# floorctrl.net
KiCad netlist of a schematic drawn in Altium Designer
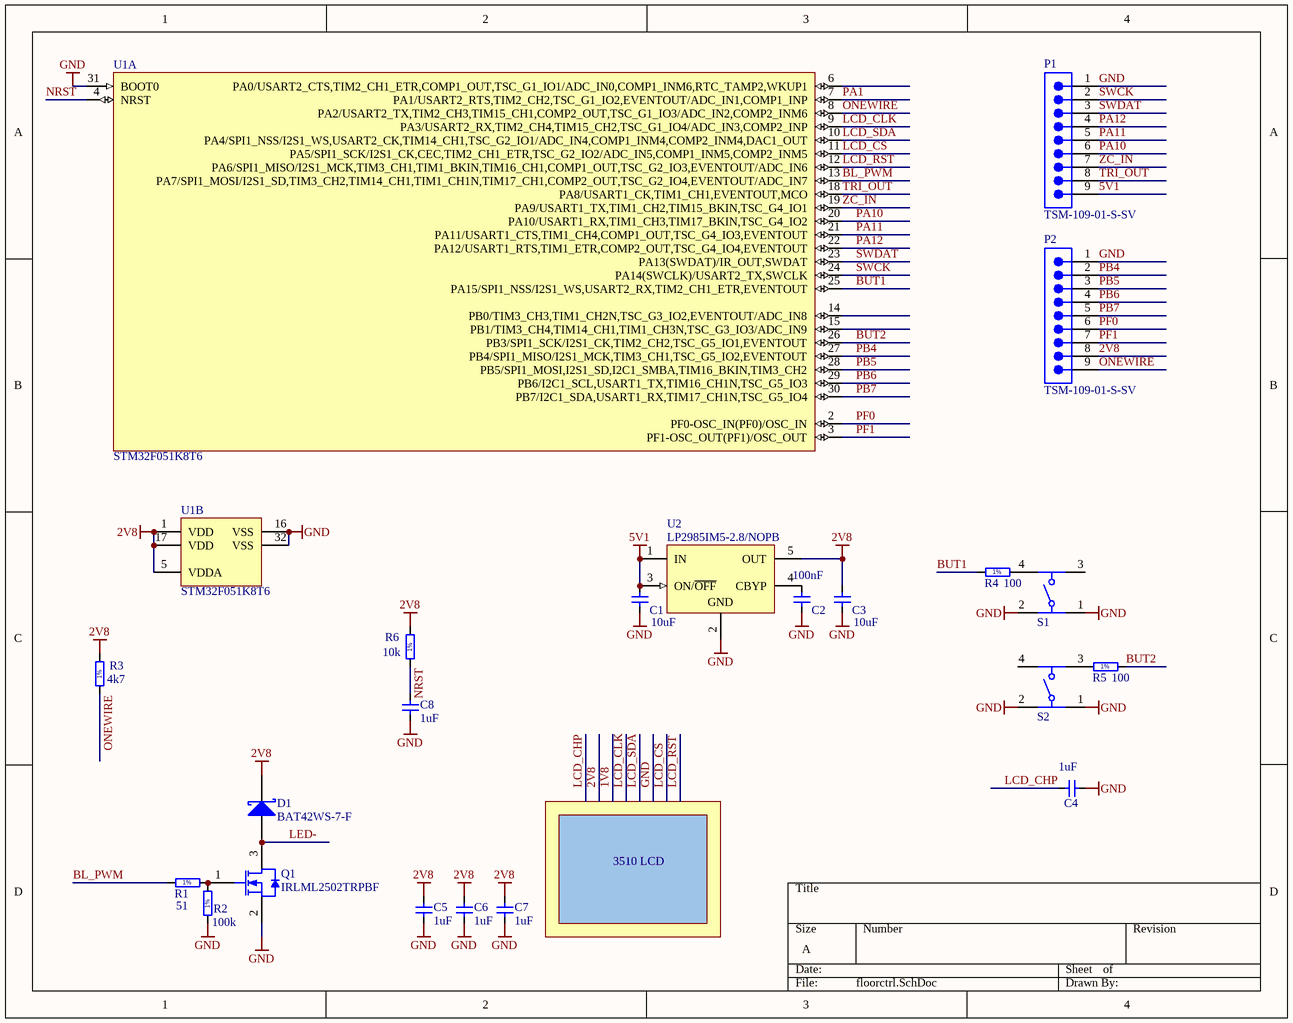
[diagram p0: floorctrl.SchDoc]

(export (version "E")
  (design (tool "Eeschema 10.0.6"))
  (components
    (comp (ref "C1")
      (value "10uF")
      (footprint "CAP0805R")
      (fields
        (field (name "PART NUMBER") "CC0805_10UF_16V_10%_X5R")
        (field (name "VOLTAGE") "16V")
        (field (name "TOLERANCE") "±10%")
        (field (name "AUTHOR") "I. Kuznetsov")
      )
      (libsource (lib "Capacitor") (part "CAP_NON_POLAR"))
    )
    (comp (ref "C2")
      (value "100nF")
      (footprint "CAP0805R")
      (fields
        (field (name "PART NUMBER") "CC0805_100NF_50V_10%_X7R")
        (field (name "VOLTAGE") "50V")
        (field (name "TOLERANCE") "±10%")
        (field (name "AUTHOR") "I. Kuznetsov")
      )
      (libsource (lib "Capacitor") (part "CAP_NON_POLAR"))
    )
    (comp (ref "C3")
      (value "10uF")
      (footprint "CAP0805R")
      (fields
        (field (name "PART NUMBER") "CC0805_10UF_16V_10%_X5R")
        (field (name "VOLTAGE") "16V")
        (field (name "TOLERANCE") "±10%")
        (field (name "AUTHOR") "I. Kuznetsov")
      )
      (libsource (lib "Capacitor") (part "CAP_NON_POLAR"))
    )
    (comp (ref "C4")
      (value "1uF")
      (footprint "CAP0805R")
      (fields
        (field (name "PART NUMBER") "CC0805_1UF_16V_10%_X7R")
        (field (name "VOLTAGE") "16V")
        (field (name "TOLERANCE") "±10%")
        (field (name "AUTHOR") "I. Kuznetsov")
      )
      (libsource (lib "Capacitor") (part "CAP_NON_POLAR"))
    )
    (comp (ref "C5")
      (value "1uF")
      (footprint "CAP0805R")
      (fields
        (field (name "PART NUMBER") "CC0805_1UF_16V_10%_X7R")
        (field (name "VOLTAGE") "16V")
        (field (name "TOLERANCE") "±10%")
        (field (name "AUTHOR") "I. Kuznetsov")
      )
      (libsource (lib "Capacitor") (part "CAP_NON_POLAR"))
    )
    (comp (ref "C6")
      (value "1uF")
      (footprint "CAP0805R")
      (fields
        (field (name "PART NUMBER") "CC0805_1UF_16V_10%_X7R")
        (field (name "VOLTAGE") "16V")
        (field (name "TOLERANCE") "±10%")
        (field (name "AUTHOR") "I. Kuznetsov")
      )
      (libsource (lib "Capacitor") (part "CAP_NON_POLAR"))
    )
    (comp (ref "C7")
      (value "1uF")
      (footprint "CAP0805R")
      (fields
        (field (name "PART NUMBER") "CC0805_1UF_16V_10%_X7R")
        (field (name "VOLTAGE") "16V")
        (field (name "TOLERANCE") "±10%")
        (field (name "AUTHOR") "I. Kuznetsov")
      )
      (libsource (lib "Capacitor") (part "CAP_NON_POLAR"))
    )
    (comp (ref "C8")
      (value "1uF")
      (footprint "CAP0805R")
      (fields
        (field (name "PART NUMBER") "CC0805_1UF_16V_10%_X7R")
        (field (name "VOLTAGE") "16V")
        (field (name "TOLERANCE") "±10%")
        (field (name "AUTHOR") "I. Kuznetsov")
      )
      (libsource (lib "Capacitor") (part "CAP_NON_POLAR"))
    )
    (comp (ref "D1")
      (value "BAT42WS-7-F")
      (footprint "DIOD-SOD323-2_V")
      (description "Schottky Barrier Diode, 30 V, -55 to 125 degC, 2-Pin SOD323, RoHS, Tape and Reel")
      (fields (field (name "MANUFACTURER") "DiodesIncorporated"))
      (libsource (lib "Altium Content Vault") (part "DSKY-AK-2"))
    )
    (comp (ref "P1")
      (value "TSM-109-01-S-SV")
      (footprint "SMTC-TSM-109-01-X-SV")
      (description "0.025\" SQ Post Header, Surface Mount, Vertical, -55 to 125 degC, 2.54 mm Pitch, 9-Pin, Male, RoHS")
      (fields (field (name "MANUFACTURER") "Samtec"))
      (libsource (lib "Altium Content Vault") (part "SMTC-TSM-109-01-X-SV"))
    )
    (comp (ref "P2")
      (value "TSM-109-01-S-SV")
      (footprint "SMTC-TSM-109-01-X-SV")
      (description "0.025\" SQ Post Header, Surface Mount, Vertical, -55 to 125 degC, 2.54 mm Pitch, 9-Pin, Male, RoHS")
      (fields (field (name "MANUFACTURER") "Samtec"))
      (libsource (lib "Altium Content Vault") (part "SMTC-TSM-109-01-X-SV"))
    )
    (comp (ref "Q1")
      (value "IRLML2502TRPBF")
      (footprint "INTR-SOT-23-3_V")
      (description "N-Channel HEXFET(R) Power MOSFET, 20 V VDS, +/- 12 V VGS, 4.2 A, 3-Pin SOT23, RoHS, Tape and Reel")
      (fields (field (name "MANUFACTURER") "International Rectifier"))
      (libsource (lib "Altium Content Vault") (part "NEMOS-GSD-3"))
    )
    (comp (ref "R1")
      (value "51")
      (footprint "RES0805R")
      (fields
        (field (name "PART NUMBER") "R0805_51R_1%_0.125W_100PPM")
        (field (name "POWER") "0.125W")
        (field (name "TOLERANCE") "±1%")
        (field (name "AUTHOR") "CERN DEM JLC")
      )
      (libsource (lib "Resistor") (part "Resistor - 1%"))
    )
    (comp (ref "R2")
      (value "100k")
      (footprint "RES0805R")
      (fields
        (field (name "PART NUMBER") "R0805_100K_1%_0.125W_100PPM")
        (field (name "POWER") "0.125W")
        (field (name "TOLERANCE") "±1%")
        (field (name "AUTHOR") "CERN DEM JLC")
      )
      (libsource (lib "Resistor") (part "Resistor - 1%"))
    )
    (comp (ref "R3")
      (value "4k7")
      (footprint "RES0805R")
      (fields
        (field (name "PART NUMBER") "R0805_4K7_1%_0.125W_100PPM")
        (field (name "POWER") "0.125W")
        (field (name "TOLERANCE") "±1%")
        (field (name "AUTHOR") "CERN DEM JLC")
      )
      (libsource (lib "Resistor") (part "Resistor - 1%"))
    )
    (comp (ref "R4")
      (value "100")
      (footprint "RES0805R")
      (fields
        (field (name "PART NUMBER") "R0805_100R_1%_0.125W_100PPM")
        (field (name "POWER") "0.125W")
        (field (name "TOLERANCE") "±1%")
        (field (name "AUTHOR") "CERN DEM JLC")
      )
      (libsource (lib "Resistor") (part "Resistor - 1%"))
    )
    (comp (ref "R5")
      (value "100")
      (footprint "RES0805R")
      (fields
        (field (name "PART NUMBER") "R0805_100R_1%_0.125W_100PPM")
        (field (name "POWER") "0.125W")
        (field (name "TOLERANCE") "±1%")
        (field (name "AUTHOR") "CERN DEM JLC")
      )
      (libsource (lib "Resistor") (part "Resistor - 1%"))
    )
    (comp (ref "R6")
      (value "10k")
      (footprint "RES0805R")
      (fields
        (field (name "PART NUMBER") "R0805_10K_1%_0.125W_100PPM")
        (field (name "POWER") "0.125W")
        (field (name "TOLERANCE") "±1%")
        (field (name "AUTHOR") "CERN DEM JLC")
      )
      (libsource (lib "Resistor") (part "Resistor - 1%"))
    )
    (comp (ref "S1")
      (value "430476073716")
      (footprint "4304x60737x6_12x12x7.3")
      (description "WS-TATV 12x12mm washable Tact Switch, THT version")
      (fields (field (name "PUBLISHER") "Wurth Elektronik"))
      (libsource (lib "ALTIUM-WS-TATV-rev17a") (part "430476073716"))
    )
    (comp (ref "S2")
      (value "430476073716")
      (footprint "4304x60737x6_12x12x7.3")
      (description "WS-TATV 12x12mm washable Tact Switch, THT version")
      (fields (field (name "PUBLISHER") "Wurth Elektronik"))
      (libsource (lib "ALTIUM-WS-TATV-rev17a") (part "430476073716"))
    )
    (comp (ref "U1")
      (value "STM32F051K8T6")
      (footprint "STM-LQFP32_L")
      (libsource (lib "Altium Content Vault") (part "MC-ARM-STM32F051-SQ32"))
    )
    (comp (ref "U2")
      (value "LP2985IM5-2.8/NOPB")
      (footprint "DBV0005A_L")
      (description "Micropower 150 mA Low-Noise Ultra Low-Dropout Regulator, 5-pin SOT-23, Pb-Free")
      (fields (field (name "MANUFACTURER") "Texas Instruments"))
      (libsource (lib "Altium Content Vault") (part "PM-REG-LP2985-SOT5"))
    )
  )
  (nets
    (net (code "2") (name "/BL_PWM") (class "Default")
      (node (ref "R1") (pin "1") (pinfunction "1_1") (pintype "passive"))
      (node (ref "U1") (pin "13") (pinfunction "PA7/SPI1_MOSI/I2S1_SD,TIM3_CH2,TIM14_CH1,TIM1_CH1N,TIM17_CH1,COMP2_OUT,TSC_G2_IO4,EVENTOUT/ADC_IN7_13") (pintype "bidirectional"))
    )
    (net (code "3") (name "/BUT1") (class "Default")
      (node (ref "R4") (pin "1") (pinfunction "1_1") (pintype "passive"))
      (node (ref "U1") (pin "25") (pinfunction "PA15/SPI1_NSS/I2S1_WS,USART2_RX,TIM2_CH1_ETR,EVENTOUT_25") (pintype "bidirectional"))
    )
    (net (code "4") (name "/BUT2") (class "Default")
      (node (ref "R5") (pin "2") (pinfunction "2_2") (pintype "passive"))
      (node (ref "U1") (pin "26") (pinfunction "PB3/SPI1_SCK/I2S1_CK,TIM2_CH2,TSC_G5_IO1,EVENTOUT_26") (pintype "bidirectional"))
    )
    (net (code "5") (name "/LCD_CHP") (class "Default")
      (node (ref "C4") (pin "1") (pinfunction "1_1") (pintype "passive"))
    )
    (net (code "6") (name "/LCD_CLK") (class "Default")
      (node (ref "U1") (pin "9") (pinfunction "PA3/USART2_RX,TIM2_CH4,TIM15_CH2,TSC_G1_IO4/ADC_IN3,COMP2_INP_9") (pintype "bidirectional"))
    )
    (net (code "7") (name "/LCD_CS") (class "Default")
      (node (ref "U1") (pin "11") (pinfunction "PA5/SPI1_SCK/I2S1_CK,CEC,TIM2_CH1_ETR,TSC_G2_IO2/ADC_IN5,COMP1_INM5,COMP2_INM5_11") (pintype "bidirectional"))
    )
    (net (code "8") (name "/LCD_RST") (class "Default")
      (node (ref "U1") (pin "12") (pinfunction "PA6/SPI1_MISO/I2S1_MCK,TIM3_CH1,TIM1_BKIN,TIM16_CH1,COMP1_OUT,TSC_G2_IO3,EVENTOUT/ADC_IN6_12") (pintype "bidirectional"))
    )
    (net (code "9") (name "/LCD_SDA") (class "Default")
      (node (ref "U1") (pin "10") (pinfunction "PA4/SPI1_NSS/I2S1_WS,USART2_CK,TIM14_CH1,TSC_G2_IO1/ADC_IN4,COMP1_INM4,COMP2_INM4,DAC1_OUT_10") (pintype "bidirectional"))
    )
    (net (code "10") (name "/LED-") (class "Default")
      (node (ref "D1") (pin "1") (pinfunction "A_1") (pintype "passive"))
      (node (ref "Q1") (pin "3") (pinfunction "D_3") (pintype "passive"))
    )
    (net (code "11") (name "/NRST") (class "Default")
      (node (ref "C8") (pin "2") (pinfunction "2_2") (pintype "passive"))
      (node (ref "R6") (pin "1") (pinfunction "1_1") (pintype "passive"))
      (node (ref "U1") (pin "4") (pinfunction "NRST_4") (pintype "bidirectional"))
    )
    (net (code "12") (name "/ONEWIRE") (class "Default")
      (node (ref "P2") (pin "9") (pinfunction "9_9") (pintype "passive"))
      (node (ref "R3") (pin "1") (pinfunction "1_1") (pintype "passive"))
      (node (ref "U1") (pin "8") (pinfunction "PA2/USART2_TX,TIM2_CH3,TIM15_CH1,COMP2_OUT,TSC_G1_IO3/ADC_IN2,COMP2_INM6_8") (pintype "bidirectional"))
    )
    (net (code "13") (name "/PA1") (class "Default")
      (node (ref "U1") (pin "7") (pinfunction "PA1/USART2_RTS,TIM2_CH2,TSC_G1_IO2,EVENTOUT/ADC_IN1,COMP1_INP_7") (pintype "bidirectional"))
    )
    (net (code "14") (name "/PA10") (class "Default")
      (node (ref "P1") (pin "6") (pinfunction "6_6") (pintype "passive"))
      (node (ref "U1") (pin "20") (pinfunction "PA10/USART1_RX,TIM1_CH3,TIM17_BKIN,TSC_G4_IO2_20") (pintype "bidirectional"))
    )
    (net (code "15") (name "/PA11") (class "Default")
      (node (ref "P1") (pin "5") (pinfunction "5_5") (pintype "passive"))
      (node (ref "U1") (pin "21") (pinfunction "PA11/USART1_CTS,TIM1_CH4,COMP1_OUT,TSC_G4_IO3,EVENTOUT_21") (pintype "bidirectional"))
    )
    (net (code "16") (name "/PA12") (class "Default")
      (node (ref "P1") (pin "4") (pinfunction "4_4") (pintype "passive"))
      (node (ref "U1") (pin "22") (pinfunction "PA12/USART1_RTS,TIM1_ETR,COMP2_OUT,TSC_G4_IO4,EVENTOUT_22") (pintype "bidirectional"))
    )
    (net (code "17") (name "/PB4") (class "Default")
      (node (ref "P2") (pin "2") (pinfunction "2_2") (pintype "passive"))
      (node (ref "U1") (pin "27") (pinfunction "PB4/SPI1_MISO/I2S1_MCK,TIM3_CH1,TSC_G5_IO2,EVENTOUT_27") (pintype "bidirectional"))
    )
    (net (code "18") (name "/PB5") (class "Default")
      (node (ref "P2") (pin "3") (pinfunction "3_3") (pintype "passive"))
      (node (ref "U1") (pin "28") (pinfunction "PB5/SPI1_MOSI,I2S1_SD,I2C1_SMBA,TIM16_BKIN,TIM3_CH2_28") (pintype "bidirectional"))
    )
    (net (code "19") (name "/PB6") (class "Default")
      (node (ref "P2") (pin "4") (pinfunction "4_4") (pintype "passive"))
      (node (ref "U1") (pin "29") (pinfunction "PB6/I2C1_SCL,USART1_TX,TIM16_CH1N,TSC_G5_IO3_29") (pintype "bidirectional"))
    )
    (net (code "20") (name "/PB7") (class "Default")
      (node (ref "P2") (pin "5") (pinfunction "5_5") (pintype "passive"))
      (node (ref "U1") (pin "30") (pinfunction "PB7/I2C1_SDA,USART1_RX,TIM17_CH1N,TSC_G5_IO4_30") (pintype "bidirectional"))
    )
    (net (code "21") (name "/PF0") (class "Default")
      (node (ref "P2") (pin "6") (pinfunction "6_6") (pintype "passive"))
      (node (ref "U1") (pin "2") (pinfunction "PF0-OSC_IN(PF0)/OSC_IN_2") (pintype "bidirectional"))
    )
    (net (code "22") (name "/PF1") (class "Default")
      (node (ref "P2") (pin "7") (pinfunction "7_7") (pintype "passive"))
      (node (ref "U1") (pin "3") (pinfunction "PF1-OSC_OUT(PF1)/OSC_OUT_3") (pintype "bidirectional"))
    )
    (net (code "23") (name "/SWCK") (class "Default")
      (node (ref "P1") (pin "2") (pinfunction "2_2") (pintype "passive"))
      (node (ref "U1") (pin "24") (pinfunction "PA14(SWCLK)/USART2_TX,SWCLK_24") (pintype "bidirectional"))
    )
    (net (code "24") (name "/SWDAT") (class "Default")
      (node (ref "P1") (pin "3") (pinfunction "3_3") (pintype "passive"))
      (node (ref "U1") (pin "23") (pinfunction "PA13(SWDAT)/IR_OUT,SWDAT_23") (pintype "bidirectional"))
    )
    (net (code "25") (name "/TRI_OUT") (class "Default")
      (node (ref "P1") (pin "8") (pinfunction "8_8") (pintype "passive"))
      (node (ref "U1") (pin "18") (pinfunction "PA8/USART1_CK,TIM1_CH1,EVENTOUT,MCO_18") (pintype "bidirectional"))
    )
    (net (code "26") (name "/ZC_IN") (class "Default")
      (node (ref "P1") (pin "7") (pinfunction "7_7") (pintype "passive"))
      (node (ref "U1") (pin "19") (pinfunction "PA9/USART1_TX,TIM1_CH2,TIM15_BKIN,TSC_G4_IO1_19") (pintype "bidirectional"))
    )
    (net (code "27") (name "2V8") (class "Default")
      (node (ref "C3") (pin "2") (pinfunction "2_2") (pintype "passive"))
      (node (ref "C5") (pin "2") (pinfunction "2_2") (pintype "passive"))
      (node (ref "C6") (pin "2") (pinfunction "2_2") (pintype "passive"))
      (node (ref "C7") (pin "2") (pinfunction "2_2") (pintype "passive"))
      (node (ref "D1") (pin "2") (pinfunction "K_2") (pintype "passive"))
      (node (ref "P2") (pin "8") (pinfunction "8_8") (pintype "passive"))
      (node (ref "R3") (pin "2") (pinfunction "2_2") (pintype "passive"))
      (node (ref "R6") (pin "2") (pinfunction "2_2") (pintype "passive"))
      (node (ref "U1") (pin "1") (pinfunction "VDD_1") (pintype "power_in"))
      (node (ref "U1") (pin "17") (pinfunction "VDD_17") (pintype "power_in"))
      (node (ref "U1") (pin "5") (pinfunction "VDDA_5") (pintype "power_in"))
      (node (ref "U2") (pin "5") (pinfunction "OUT_5") (pintype "power_in"))
    )
    (net (code "28") (name "5V1") (class "Default")
      (node (ref "C1") (pin "2") (pinfunction "2_2") (pintype "passive"))
      (node (ref "P1") (pin "9") (pinfunction "9_9") (pintype "passive"))
      (node (ref "U2") (pin "1") (pinfunction "IN_1") (pintype "power_in"))
      (node (ref "U2") (pin "3") (pinfunction "ON/~{OFF}_3") (pintype "input"))
    )
    (net (code "29") (name "GND") (class "Default")
      (node (ref "C1") (pin "1") (pinfunction "1_1") (pintype "passive"))
      (node (ref "C2") (pin "1") (pinfunction "1_1") (pintype "passive"))
      (node (ref "C3") (pin "1") (pinfunction "1_1") (pintype "passive"))
      (node (ref "C4") (pin "2") (pinfunction "2_2") (pintype "passive"))
      (node (ref "C5") (pin "1") (pinfunction "1_1") (pintype "passive"))
      (node (ref "C6") (pin "1") (pinfunction "1_1") (pintype "passive"))
      (node (ref "C7") (pin "1") (pinfunction "1_1") (pintype "passive"))
      (node (ref "C8") (pin "1") (pinfunction "1_1") (pintype "passive"))
      (node (ref "P1") (pin "1") (pinfunction "1_1") (pintype "passive"))
      (node (ref "P2") (pin "1") (pinfunction "1_1") (pintype "passive"))
      (node (ref "Q1") (pin "2") (pinfunction "S_2") (pintype "passive"))
      (node (ref "R2") (pin "1") (pinfunction "1_1") (pintype "passive"))
      (node (ref "S1") (pin "1") (pinfunction "1_1") (pintype "passive"))
      (node (ref "S1") (pin "2") (pinfunction "2_2") (pintype "passive"))
      (node (ref "S2") (pin "1") (pinfunction "1_1") (pintype "passive"))
      (node (ref "S2") (pin "2") (pinfunction "2_2") (pintype "passive"))
      (node (ref "U1") (pin "16") (pinfunction "VSS_16") (pintype "power_in"))
      (node (ref "U1") (pin "31") (pinfunction "BOOT0_31") (pintype "input"))
      (node (ref "U1") (pin "32") (pinfunction "VSS_32") (pintype "power_in"))
      (node (ref "U2") (pin "2") (pinfunction "GND_2") (pintype "power_in"))
    )
    (net (code "30") (name "Net-(Q1-G)") (class "Default")
      (node (ref "Q1") (pin "1") (pinfunction "G_1") (pintype "passive"))
      (node (ref "R1") (pin "2") (pinfunction "2_2") (pintype "passive"))
      (node (ref "R2") (pin "2") (pinfunction "2_2") (pintype "passive"))
    )
    (net (code "31") (name "Net-(R4-Pad2)") (class "Default")
      (node (ref "R4") (pin "2") (pinfunction "2_2") (pintype "passive"))
      (node (ref "S1") (pin "4") (pinfunction "4_4") (pintype "passive"))
    )
    (net (code "32") (name "Net-(R5-Pad1)") (class "Default")
      (node (ref "R5") (pin "1") (pinfunction "1_1") (pintype "passive"))
      (node (ref "S2") (pin "3") (pinfunction "3_3") (pintype "passive"))
    )
    (net (code "33") (name "Net-(U2-CBYP)") (class "Default")
      (node (ref "C2") (pin "2") (pinfunction "2_2") (pintype "passive"))
      (node (ref "U2") (pin "4") (pinfunction "CBYP_4") (pintype "passive"))
    )
    (net (code "34") (name "unconnected-(S1-Pad3)") (class "Default")
      (node (ref "S1") (pin "3") (pinfunction "3_3") (pintype "passive"))
    )
    (net (code "35") (name "unconnected-(S2-Pad4)") (class "Default")
      (node (ref "S2") (pin "4") (pinfunction "4_4") (pintype "passive"))
    )
    (net (code "36") (name "unconnected-(U1A-PA0{slash}USART2_CTS,TIM2_CH1_ETR,COMP1_OUT,TSC_G1_IO1{slash}ADC_IN0,COMP1_INM6,RTC_TAMP2,WKUP1-Pad6)") (class "Default")
      (node (ref "U1") (pin "6") (pinfunction "PA0/USART2_CTS,TIM2_CH1_ETR,COMP1_OUT,TSC_G1_IO1/ADC_IN0,COMP1_INM6,RTC_TAMP2,WKUP1_6") (pintype "bidirectional"))
    )
    (net (code "37") (name "unconnected-(U1A-PB0{slash}TIM3_CH3,TIM1_CH2N,TSC_G3_IO2,EVENTOUT{slash}ADC_IN8-Pad14)") (class "Default")
      (node (ref "U1") (pin "14") (pinfunction "PB0/TIM3_CH3,TIM1_CH2N,TSC_G3_IO2,EVENTOUT/ADC_IN8_14") (pintype "bidirectional"))
    )
    (net (code "38") (name "unconnected-(U1A-PB1{slash}TIM3_CH4,TIM14_CH1,TIM1_CH3N,TSC_G3_IO3{slash}ADC_IN9-Pad15)") (class "Default")
      (node (ref "U1") (pin "15") (pinfunction "PB1/TIM3_CH4,TIM14_CH1,TIM1_CH3N,TSC_G3_IO3/ADC_IN9_15") (pintype "bidirectional"))
    )
  )
)
